# Smart_water_dispenser.net
KiCad netlist of a schematic drawn in Altium Designer
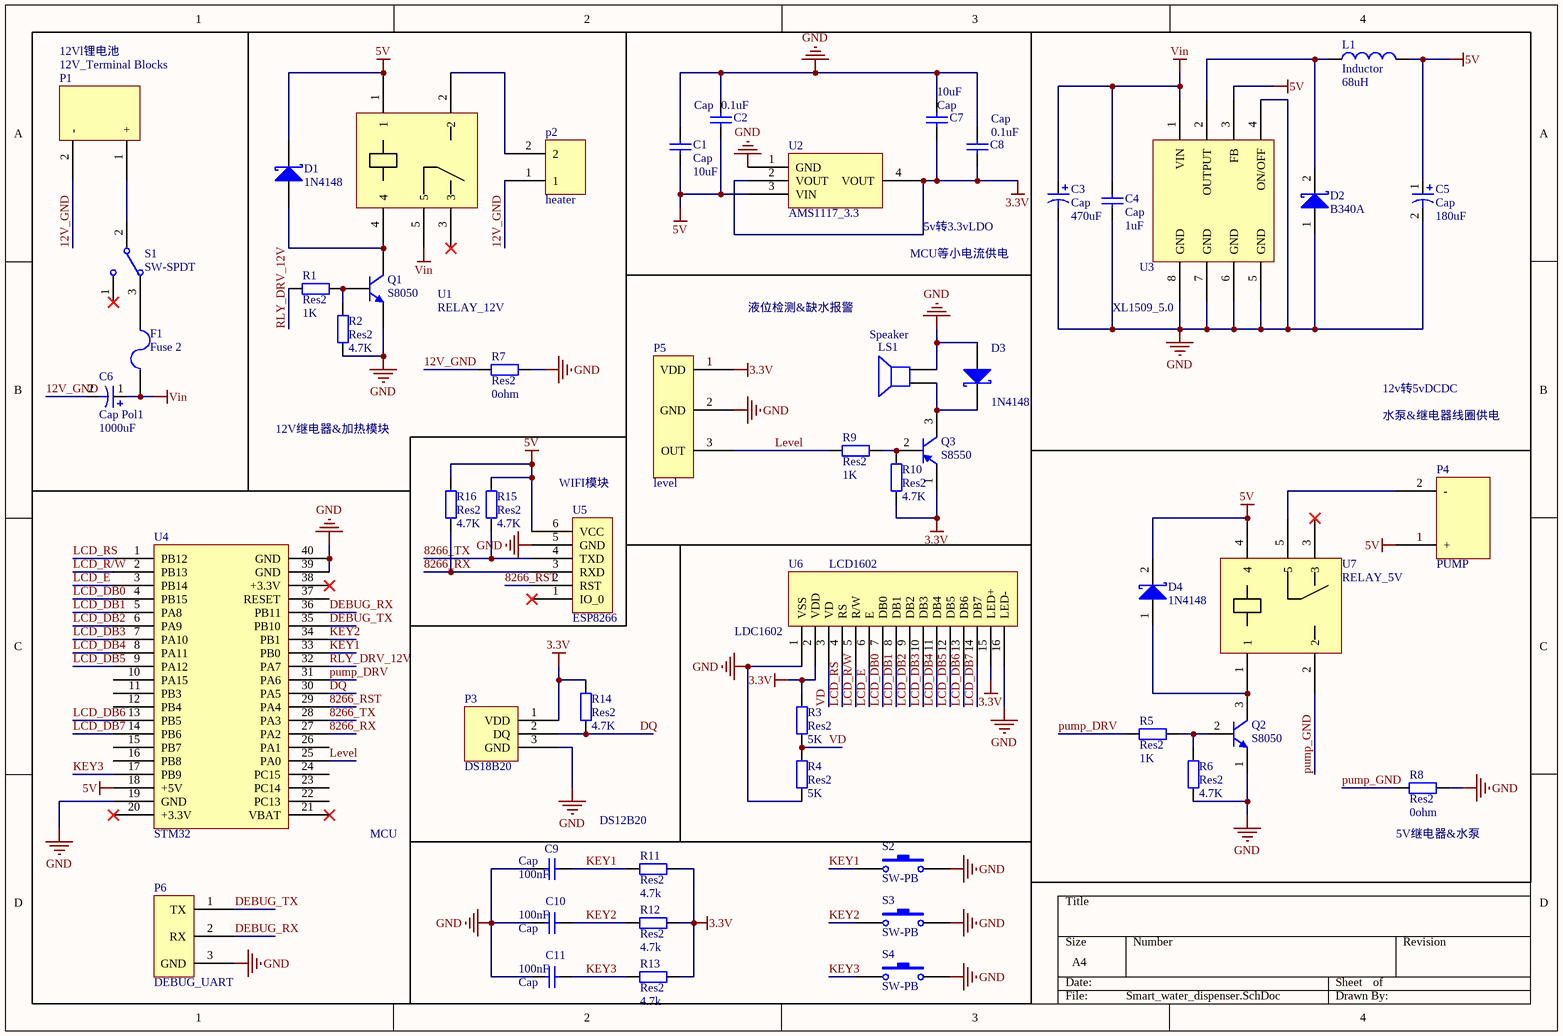
[diagram p0: Smart_water_dispenser.SchDoc]

(export (version "E")
  (design (tool "Eeschema 10.0.6"))
  (components
    (comp (ref "C1")
      (value "Cap")
      (footprint "0805")
      (description "Capacitor")
      (fields (field (name "ALTIUM_VALUE") "10uF") (field (name "PUBLISHER") "Altium Limited"))
      (libsource (lib "Miscellaneous Devices") (part "Cap"))
    )
    (comp (ref "C2")
      (value "Cap")
      (footprint "0805")
      (description "Capacitor")
      (fields (field (name "ALTIUM_VALUE") "0.1uF") (field (name "PUBLISHER") "Altium Limited"))
      (libsource (lib "Miscellaneous Devices") (part "Cap"))
    )
    (comp (ref "C3")
      (value "Cap")
      (footprint "CAP_TH_BD10")
      (description "Polarized Capacitor (Radial)")
      (fields (field (name "ALTIUM_VALUE") "470uF") (field (name "PUBLISHER") "Altium Limited"))
      (libsource (lib "") (part "Cap Pol1_1"))
    )
    (comp (ref "C4")
      (value "Cap")
      (footprint "0805")
      (description "Capacitor")
      (fields (field (name "ALTIUM_VALUE") "1uF") (field (name "PUBLISHER") "Altium Limited"))
      (libsource (lib "Miscellaneous Devices") (part "Cap"))
    )
    (comp (ref "C5")
      (value "Cap")
      (footprint "CAP_TH_BD10")
      (description "Polarized Capacitor (Radial)")
      (fields (field (name "ALTIUM_VALUE") "180uF") (field (name "PUBLISHER") "Altium Limited"))
      (libsource (lib "Miscellaneous Devices") (part "Cap Pol1"))
    )
    (comp (ref "C6")
      (value "Cap Pol1")
      (footprint "cap_1000uF")
      (description "Polarized Capacitor (Radial)")
      (fields (field (name "ALTIUM_VALUE") "1000uF") (field (name "PUBLISHER") "Altium Limited"))
      (libsource (lib "Miscellaneous Devices") (part "Cap Pol1"))
    )
    (comp (ref "C7")
      (value "Cap")
      (footprint "0805")
      (description "Capacitor")
      (fields (field (name "ALTIUM_VALUE") "10uF") (field (name "PUBLISHER") "Altium Limited"))
      (libsource (lib "Miscellaneous Devices") (part "Cap"))
    )
    (comp (ref "C8")
      (value "Cap")
      (footprint "0805")
      (description "Capacitor")
      (fields (field (name "ALTIUM_VALUE") "0.1uF") (field (name "PUBLISHER") "Altium Limited"))
      (libsource (lib "Miscellaneous Devices") (part "Cap"))
    )
    (comp (ref "C9")
      (value "Cap")
      (footprint "0805")
      (description "Capacitor")
      (fields (field (name "ALTIUM_VALUE") "100nF") (field (name "PUBLISHER") "Altium Limited"))
      (libsource (lib "Miscellaneous Devices") (part "Cap"))
    )
    (comp (ref "C10")
      (value "Cap")
      (footprint "0805")
      (description "Capacitor")
      (fields (field (name "ALTIUM_VALUE") "100nF") (field (name "PUBLISHER") "Altium Limited"))
      (libsource (lib "Miscellaneous Devices") (part "Cap"))
    )
    (comp (ref "C11")
      (value "Cap")
      (footprint "0805")
      (description "Capacitor")
      (fields (field (name "ALTIUM_VALUE") "100nF") (field (name "PUBLISHER") "Altium Limited"))
      (libsource (lib "Miscellaneous Devices") (part "Cap"))
    )
    (comp (ref "D1")
      (value "1N4148")
      (footprint "1N4148")
      (description "Schottky Diode")
      (fields (field (name "PUBLISHER") "Altium Limited"))
      (libsource (lib "") (part "D Schottky_1"))
    )
    (comp (ref "D2")
      (value "B340A")
      (footprint "B340A")
      (description "Schottky Diode")
      (fields (field (name "PUBLISHER") "Altium Limited"))
      (libsource (lib "Miscellaneous Devices") (part "D Schottky"))
    )
    (comp (ref "D3")
      (value "1N4148")
      (footprint "1N4148")
      (description "Schottky Diode")
      (fields (field (name "PUBLISHER") "Altium Limited"))
      (libsource (lib "") (part "D Schottky_1"))
    )
    (comp (ref "D4")
      (value "1N4148")
      (footprint "1N4148")
      (description "Schottky Diode")
      (fields (field (name "PUBLISHER") "Altium Limited"))
      (libsource (lib "Miscellaneous Devices") (part "D Schottky"))
    )
    (comp (ref "F1")
      (value "Fuse 2")
      (footprint "F1812")
      (description "Fuse")
      (fields (field (name "PUBLISHER") "Altium Limited"))
      (libsource (lib "Miscellaneous Devices") (part "Fuse 2"))
    )
    (comp (ref "L1")
      (value "Inductor")
      (footprint "IND_CD54")
      (fields (field (name "ALTIUM_VALUE") "68uH") (field (name "PUBLISHER") "Altium Limited"))
      (libsource (lib "Miscellaneous Devices") (part "Inductor"))
    )
    (comp (ref "LS1")
      (value "Speaker")
      (footprint "buzzer")
      (description "Loudspeaker")
      (fields (field (name "PUBLISHER") "Altium Limited"))
      (libsource (lib "Miscellaneous Devices") (part "Speaker"))
    )
    (comp (ref "P1")
      (value "12V_Terminal Blocks")
      (footprint "2PIN")
      (libsource (lib "智能饮水机") (part "12V_Terminal Blocks"))
    )
    (comp (ref "p2") (value "heater") (footprint "2PIN") (libsource (lib "智能饮水机") (part "heater")))
    (comp (ref "P3") (value "DS18B20") (footprint "DS18B20") (libsource (lib "智能饮水机") (part "DS18B20")))
    (comp (ref "P4") (value "PUMP") (footprint "2PIN") (libsource (lib "智能饮水机") (part "PUMP")))
    (comp (ref "P5") (value "level") (footprint "DS18B20") (libsource (lib "智能饮水机") (part "level")))
    (comp (ref "P6")
      (value "DEBUG_UART")
      (footprint "DEBUG_UART")
      (libsource (lib "智能饮水机") (part "DEBUG_UART"))
    )
    (comp (ref "Q1")
      (value "S8050")
      (footprint "S8050")
      (description "NPN General Purpose Amplifier")
      (fields (field (name "PUBLISHER") "Altium Limited"))
      (libsource (lib "Miscellaneous Devices") (part "2N3904"))
    )
    (comp (ref "Q2")
      (value "S8050")
      (footprint "S8050")
      (description "NPN General Purpose Amplifier")
      (fields (field (name "PUBLISHER") "Altium Limited"))
      (libsource (lib "") (part "2N3904_1"))
    )
    (comp (ref "Q3")
      (value "S8550")
      (footprint "S8050")
      (description "PNP General Purpose Amplifier")
      (fields (field (name "PUBLISHER") "Altium Limited"))
      (libsource (lib "Miscellaneous Devices") (part "2N3906"))
    )
    (comp (ref "R1")
      (value "Res2")
      (footprint "0805")
      (description "Resistor")
      (fields (field (name "ALTIUM_VALUE") "1K") (field (name "PUBLISHER") "Altium Limited"))
      (libsource (lib "Miscellaneous Devices") (part "Res2"))
    )
    (comp (ref "R2")
      (value "Res2")
      (footprint "0805")
      (description "Resistor")
      (fields (field (name "ALTIUM_VALUE") "4.7K") (field (name "PUBLISHER") "Altium Limited"))
      (libsource (lib "") (part "Res2_2"))
    )
    (comp (ref "R3")
      (value "Res2")
      (footprint "0805")
      (description "Resistor")
      (fields (field (name "ALTIUM_VALUE") "5K") (field (name "PUBLISHER") "Altium Limited"))
      (libsource (lib "") (part "Res2_2"))
    )
    (comp (ref "R4")
      (value "Res2")
      (footprint "0805")
      (description "Resistor")
      (fields (field (name "ALTIUM_VALUE") "5K") (field (name "PUBLISHER") "Altium Limited"))
      (libsource (lib "") (part "Res2_2"))
    )
    (comp (ref "R5")
      (value "Res2")
      (footprint "0805")
      (description "Resistor")
      (fields (field (name "ALTIUM_VALUE") "1K") (field (name "PUBLISHER") "Altium Limited"))
      (libsource (lib "Miscellaneous Devices") (part "Res2"))
    )
    (comp (ref "R6")
      (value "Res2")
      (footprint "0805")
      (description "Resistor")
      (fields (field (name "ALTIUM_VALUE") "4.7K") (field (name "PUBLISHER") "Altium Limited"))
      (libsource (lib "") (part "Res2_2"))
    )
    (comp (ref "R7")
      (value "Res2")
      (footprint "0805")
      (description "Resistor")
      (fields (field (name "ALTIUM_VALUE") "0ohm") (field (name "PUBLISHER") "Altium Limited"))
      (libsource (lib "Miscellaneous Devices") (part "Res2"))
    )
    (comp (ref "R8")
      (value "Res2")
      (footprint "0805")
      (description "Resistor")
      (fields (field (name "ALTIUM_VALUE") "0ohm") (field (name "PUBLISHER") "Altium Limited"))
      (libsource (lib "Miscellaneous Devices") (part "Res2"))
    )
    (comp (ref "R9")
      (value "Res2")
      (footprint "0805")
      (description "Resistor")
      (fields (field (name "ALTIUM_VALUE") "1K") (field (name "PUBLISHER") "Altium Limited"))
      (libsource (lib "Miscellaneous Devices") (part "Res2"))
    )
    (comp (ref "R10")
      (value "Res2")
      (footprint "0805")
      (description "Resistor")
      (fields (field (name "ALTIUM_VALUE") "4.7K") (field (name "PUBLISHER") "Altium Limited"))
      (libsource (lib "") (part "Res2_2"))
    )
    (comp (ref "R11")
      (value "Res2")
      (footprint "0805")
      (description "Resistor")
      (fields (field (name "ALTIUM_VALUE") "4.7k") (field (name "PUBLISHER") "Altium Limited"))
      (libsource (lib "") (part "Res2_1"))
    )
    (comp (ref "R12")
      (value "Res2")
      (footprint "0805")
      (description "Resistor")
      (fields (field (name "ALTIUM_VALUE") "4.7k") (field (name "PUBLISHER") "Altium Limited"))
      (libsource (lib "") (part "Res2_1"))
    )
    (comp (ref "R13")
      (value "Res2")
      (footprint "0805")
      (description "Resistor")
      (fields (field (name "ALTIUM_VALUE") "4.7k") (field (name "PUBLISHER") "Altium Limited"))
      (libsource (lib "") (part "Res2_1"))
    )
    (comp (ref "R14")
      (value "Res2")
      (footprint "0805")
      (description "Resistor")
      (fields (field (name "ALTIUM_VALUE") "4.7K") (field (name "PUBLISHER") "Altium Limited"))
      (libsource (lib "") (part "Res2_2"))
    )
    (comp (ref "R15")
      (value "Res2")
      (footprint "0805")
      (description "Resistor")
      (fields (field (name "ALTIUM_VALUE") "4.7K") (field (name "PUBLISHER") "Altium Limited"))
      (libsource (lib "") (part "Res2_2"))
    )
    (comp (ref "R16")
      (value "Res2")
      (footprint "0805")
      (description "Resistor")
      (fields (field (name "ALTIUM_VALUE") "4.7K") (field (name "PUBLISHER") "Altium Limited"))
      (libsource (lib "") (part "Res2_2"))
    )
    (comp (ref "S1")
      (value "SW-SPDT")
      (footprint "SW")
      (description "SPDT Subminiature Toggle Switch, Right Angle Mounting, Vertical Actuation")
      (fields (field (name "PUBLISHER") "Altium Limited"))
      (libsource (lib "Miscellaneous Devices") (part "SW-SPDT"))
    )
    (comp (ref "S2")
      (value "SW-PB")
      (footprint "SW2")
      (description "Switch")
      (fields (field (name "PUBLISHER") "Altium Limited"))
      (libsource (lib "Miscellaneous Devices") (part "SW-PB"))
    )
    (comp (ref "S3")
      (value "SW-PB")
      (footprint "SW2")
      (description "Switch")
      (fields (field (name "PUBLISHER") "Altium Limited"))
      (libsource (lib "Miscellaneous Devices") (part "SW-PB"))
    )
    (comp (ref "S4")
      (value "SW-PB")
      (footprint "SW2")
      (description "Switch")
      (fields (field (name "PUBLISHER") "Altium Limited"))
      (libsource (lib "Miscellaneous Devices") (part "SW-PB"))
    )
    (comp (ref "U1") (value "RELAY_12V") (footprint "RELAY") (libsource (lib "智能饮水机") (part "RELAY_12V")))
    (comp (ref "U2")
      (value "AMS1117_3.3")
      (footprint "AMS1117")
      (libsource (lib "智能饮水机") (part "AMS1117_3.3"))
    )
    (comp (ref "U3")
      (value "XL1509_5.0")
      (footprint "XL1509_5.0")
      (libsource (lib "智能饮水机") (part "XL1509_5.0"))
    )
    (comp (ref "U4") (value "STM32") (footprint "STM32") (libsource (lib "智能饮水机") (part "STM32")))
    (comp (ref "U5") (value "ESP8266") (footprint "ESP8266") (libsource (lib "智能饮水机") (part "ESP8266")))
    (comp (ref "U6") (value "LCD1602") (footprint "LCD1602") (libsource (lib "智能饮水机") (part "LCD1602")))
    (comp (ref "U7") (value "RELAY_5V") (footprint "RELAY") (libsource (lib "智能饮水机") (part "RELAY_5V")))
  )
  (nets
    (net (code "1") (name "/12V_GND") (class "Default")
      (node (ref "C6") (pin "2") (pinfunction "2_2") (pintype "passive"))
      (node (ref "P1") (pin "2") (pinfunction "-_2") (pintype "passive"))
      (node (ref "R7") (pin "1") (pinfunction "1_1") (pintype "passive"))
      (node (ref "p2") (pin "1") (pinfunction "1_1") (pintype "passive"))
    )
    (net (code "2") (name "/8266_RST") (class "Default")
      (node (ref "U4") (pin "29") (pinfunction "PA4_29") (pintype "passive"))
      (node (ref "U5") (pin "2") (pinfunction "RST_2") (pintype "passive"))
    )
    (net (code "3") (name "/8266_RX") (class "Default")
      (node (ref "R16") (pin "1") (pinfunction "1_1") (pintype "passive"))
      (node (ref "U4") (pin "27") (pinfunction "PA2_27") (pintype "passive"))
      (node (ref "U5") (pin "3") (pinfunction "RXD_3") (pintype "passive"))
    )
    (net (code "4") (name "/8266_TX") (class "Default")
      (node (ref "R15") (pin "1") (pinfunction "1_1") (pintype "passive"))
      (node (ref "U4") (pin "28") (pinfunction "PA3_28") (pintype "passive"))
      (node (ref "U5") (pin "4") (pinfunction "TXD_4") (pintype "passive"))
    )
    (net (code "5") (name "/DEBUG_RX") (class "Default")
      (node (ref "P6") (pin "2") (pinfunction "RX_2") (pintype "passive"))
      (node (ref "U4") (pin "36") (pinfunction "PB11_36") (pintype "passive"))
    )
    (net (code "6") (name "/DEBUG_TX") (class "Default")
      (node (ref "P6") (pin "1") (pinfunction "TX_1") (pintype "passive"))
      (node (ref "U4") (pin "35") (pinfunction "PB10_35") (pintype "passive"))
    )
    (net (code "7") (name "/DQ") (class "Default")
      (node (ref "P3") (pin "2") (pinfunction "DQ_2") (pintype "passive"))
      (node (ref "R14") (pin "1") (pinfunction "1_1") (pintype "passive"))
      (node (ref "U4") (pin "30") (pinfunction "PA5_30") (pintype "passive"))
    )
    (net (code "8") (name "/KEY1") (class "Default")
      (node (ref "C9") (pin "2") (pinfunction "2_2") (pintype "passive"))
      (node (ref "R11") (pin "2") (pinfunction "2_2") (pintype "passive"))
      (node (ref "S2") (pin "1") (pinfunction "1_1") (pintype "passive"))
      (node (ref "U4") (pin "33") (pinfunction "PB0_33") (pintype "passive"))
    )
    (net (code "9") (name "/KEY2") (class "Default")
      (node (ref "C10") (pin "2") (pinfunction "2_2") (pintype "passive"))
      (node (ref "R12") (pin "2") (pinfunction "2_2") (pintype "passive"))
      (node (ref "S3") (pin "1") (pinfunction "1_1") (pintype "passive"))
      (node (ref "U4") (pin "34") (pinfunction "PB1_34") (pintype "passive"))
    )
    (net (code "10") (name "/KEY3") (class "Default")
      (node (ref "C11") (pin "2") (pinfunction "2_2") (pintype "passive"))
      (node (ref "R13") (pin "2") (pinfunction "2_2") (pintype "passive"))
      (node (ref "S4") (pin "1") (pinfunction "1_1") (pintype "passive"))
      (node (ref "U4") (pin "17") (pinfunction "PB9_17") (pintype "passive"))
    )
    (net (code "11") (name "/LCD_DB0") (class "Default")
      (node (ref "U4") (pin "4") (pinfunction "PB15_4") (pintype "passive"))
      (node (ref "U6") (pin "7") (pinfunction "DB0_7") (pintype "passive"))
    )
    (net (code "12") (name "/LCD_DB1") (class "Default")
      (node (ref "U4") (pin "5") (pinfunction "PA8_5") (pintype "passive"))
      (node (ref "U6") (pin "8") (pinfunction "DB1_8") (pintype "passive"))
    )
    (net (code "13") (name "/LCD_DB2") (class "Default")
      (node (ref "U4") (pin "6") (pinfunction "PA9_6") (pintype "passive"))
      (node (ref "U6") (pin "9") (pinfunction "DB2_9") (pintype "passive"))
    )
    (net (code "14") (name "/LCD_DB3") (class "Default")
      (node (ref "U4") (pin "7") (pinfunction "PA10_7") (pintype "passive"))
      (node (ref "U6") (pin "10") (pinfunction "DB3_10") (pintype "passive"))
    )
    (net (code "15") (name "/LCD_DB4") (class "Default")
      (node (ref "U4") (pin "8") (pinfunction "PA11_8") (pintype "passive"))
      (node (ref "U6") (pin "11") (pinfunction "DB4_11") (pintype "passive"))
    )
    (net (code "16") (name "/LCD_DB5") (class "Default")
      (node (ref "U4") (pin "9") (pinfunction "PA12_9") (pintype "passive"))
      (node (ref "U6") (pin "12") (pinfunction "DB5_12") (pintype "passive"))
    )
    (net (code "17") (name "/LCD_DB6") (class "Default")
      (node (ref "U4") (pin "13") (pinfunction "PB5_13") (pintype "passive"))
      (node (ref "U6") (pin "13") (pinfunction "DB6_13") (pintype "passive"))
    )
    (net (code "18") (name "/LCD_DB7") (class "Default")
      (node (ref "U4") (pin "14") (pinfunction "PB6_14") (pintype "passive"))
      (node (ref "U6") (pin "14") (pinfunction "DB7_14") (pintype "passive"))
    )
    (net (code "19") (name "/LCD_E") (class "Default")
      (node (ref "U4") (pin "3") (pinfunction "PB14_3") (pintype "passive"))
      (node (ref "U6") (pin "6") (pinfunction "E_6") (pintype "passive"))
    )
    (net (code "20") (name "/LCD_RS") (class "Default")
      (node (ref "U4") (pin "1") (pinfunction "PB12_1") (pintype "passive"))
      (node (ref "U6") (pin "4") (pinfunction "RS_4") (pintype "passive"))
    )
    (net (code "21") (name "/LCD_R{slash}W") (class "Default")
      (node (ref "U4") (pin "2") (pinfunction "PB13_2") (pintype "passive"))
      (node (ref "U6") (pin "5") (pinfunction "R/W_5") (pintype "passive"))
    )
    (net (code "22") (name "/Level") (class "Default")
      (node (ref "P5") (pin "3") (pinfunction "OUT_3") (pintype "passive"))
      (node (ref "R9") (pin "1") (pinfunction "1_1") (pintype "passive"))
      (node (ref "U4") (pin "25") (pinfunction "PA0_25") (pintype "passive"))
    )
    (net (code "23") (name "/RLY_DRV_12V") (class "Default")
      (node (ref "R1") (pin "1") (pinfunction "1_1") (pintype "passive"))
      (node (ref "U4") (pin "32") (pinfunction "PA7_32") (pintype "passive"))
    )
    (net (code "24") (name "/VD") (class "Default")
      (node (ref "R3") (pin "1") (pinfunction "1_1") (pintype "passive"))
      (node (ref "R4") (pin "2") (pinfunction "2_2") (pintype "passive"))
      (node (ref "U6") (pin "3") (pinfunction "VD_3") (pintype "passive"))
    )
    (net (code "25") (name "/pump_DRV") (class "Default")
      (node (ref "R5") (pin "1") (pinfunction "1_1") (pintype "passive"))
      (node (ref "U4") (pin "31") (pinfunction "PA6_31") (pintype "passive"))
    )
    (net (code "26") (name "/pump_GND") (class "Default")
      (node (ref "R8") (pin "1") (pinfunction "1_1") (pintype "passive"))
      (node (ref "U7") (pin "2") (pinfunction "2_2") (pintype "passive"))
    )
    (net (code "27") (name "3.3V") (class "Default")
      (node (ref "C7") (pin "1") (pinfunction "1_1") (pintype "passive"))
      (node (ref "C8") (pin "1") (pinfunction "1_1") (pintype "passive"))
      (node (ref "P3") (pin "1") (pinfunction "VDD_1") (pintype "passive"))
      (node (ref "P5") (pin "1") (pinfunction "VDD_1") (pintype "passive"))
      (node (ref "Q3") (pin "1") (pinfunction "E_1") (pintype "passive"))
      (node (ref "R10") (pin "1") (pinfunction "1_1") (pintype "passive"))
      (node (ref "R11") (pin "1") (pinfunction "1_1") (pintype "passive"))
      (node (ref "R12") (pin "1") (pinfunction "1_1") (pintype "passive"))
      (node (ref "R13") (pin "1") (pinfunction "1_1") (pintype "passive"))
      (node (ref "R14") (pin "2") (pinfunction "2_2") (pintype "passive"))
      (node (ref "R3") (pin "2") (pinfunction "2_2") (pintype "passive"))
      (node (ref "U2") (pin "2") (pinfunction "VOUT_2") (pintype "passive"))
      (node (ref "U2") (pin "4") (pinfunction "VOUT_4") (pintype "passive"))
      (node (ref "U6") (pin "15") (pinfunction "LED+_15") (pintype "passive"))
      (node (ref "U6") (pin "2") (pinfunction "VDD_2") (pintype "passive"))
    )
    (net (code "28") (name "5V") (class "Default")
      (node (ref "C1") (pin "2") (pinfunction "2_2") (pintype "passive"))
      (node (ref "C2") (pin "1") (pinfunction "1_1") (pintype "passive"))
      (node (ref "C5") (pin "1") (pinfunction "1_1") (pintype "passive"))
      (node (ref "D1") (pin "2") (pinfunction "K_2") (pintype "passive"))
      (node (ref "D4") (pin "2") (pinfunction "K_2") (pintype "passive"))
      (node (ref "L1") (pin "2") (pinfunction "2_2") (pintype "passive"))
      (node (ref "P4") (pin "1") (pinfunction "+_1") (pintype "passive"))
      (node (ref "R15") (pin "2") (pinfunction "2_2") (pintype "passive"))
      (node (ref "R16") (pin "2") (pinfunction "2_2") (pintype "passive"))
      (node (ref "U1") (pin "1") (pinfunction "1_1") (pintype "passive"))
      (node (ref "U2") (pin "3") (pinfunction "VIN_3") (pintype "passive"))
      (node (ref "U3") (pin "3") (pinfunction "FB_3") (pintype "passive"))
      (node (ref "U4") (pin "18") (pinfunction "+5V_18") (pintype "passive"))
      (node (ref "U5") (pin "6") (pinfunction "VCC_6") (pintype "passive"))
      (node (ref "U7") (pin "4") (pinfunction "4_4") (pintype "passive"))
    )
    (net (code "29") (name "GND") (class "Default")
      (node (ref "C1") (pin "1") (pinfunction "1_1") (pintype "passive"))
      (node (ref "C10") (pin "1") (pinfunction "1_1") (pintype "passive"))
      (node (ref "C11") (pin "1") (pinfunction "1_1") (pintype "passive"))
      (node (ref "C2") (pin "2") (pinfunction "2_2") (pintype "passive"))
      (node (ref "C3") (pin "2") (pinfunction "2_2") (pintype "passive"))
      (node (ref "C4") (pin "1") (pinfunction "1_1") (pintype "passive"))
      (node (ref "C5") (pin "2") (pinfunction "2_2") (pintype "passive"))
      (node (ref "C7") (pin "2") (pinfunction "2_2") (pintype "passive"))
      (node (ref "C8") (pin "2") (pinfunction "2_2") (pintype "passive"))
      (node (ref "C9") (pin "1") (pinfunction "1_1") (pintype "passive"))
      (node (ref "D2") (pin "1") (pinfunction "A_1") (pintype "passive"))
      (node (ref "D3") (pin "1") (pinfunction "A_1") (pintype "passive"))
      (node (ref "LS1") (pin "2") (pinfunction "2_2") (pintype "passive"))
      (node (ref "P3") (pin "3") (pinfunction "GND_3") (pintype "passive"))
      (node (ref "P5") (pin "2") (pinfunction "GND_2") (pintype "passive"))
      (node (ref "P6") (pin "3") (pinfunction "GND_3") (pintype "passive"))
      (node (ref "Q1") (pin "1") (pinfunction "E_1") (pintype "passive"))
      (node (ref "Q2") (pin "1") (pinfunction "E_1") (pintype "passive"))
      (node (ref "R2") (pin "1") (pinfunction "1_1") (pintype "passive"))
      (node (ref "R4") (pin "1") (pinfunction "1_1") (pintype "passive"))
      (node (ref "R6") (pin "1") (pinfunction "1_1") (pintype "passive"))
      (node (ref "R7") (pin "2") (pinfunction "2_2") (pintype "passive"))
      (node (ref "R8") (pin "2") (pinfunction "2_2") (pintype "passive"))
      (node (ref "S2") (pin "2") (pinfunction "2_2") (pintype "passive"))
      (node (ref "S3") (pin "2") (pinfunction "2_2") (pintype "passive"))
      (node (ref "S4") (pin "2") (pinfunction "2_2") (pintype "passive"))
      (node (ref "U2") (pin "1") (pinfunction "GND_1") (pintype "passive"))
      (node (ref "U3") (pin "4") (pinfunction "ON/OFF_4") (pintype "passive"))
      (node (ref "U3") (pin "5") (pinfunction "GND_5") (pintype "passive"))
      (node (ref "U3") (pin "6") (pinfunction "GND_6") (pintype "passive"))
      (node (ref "U3") (pin "7") (pinfunction "GND_7") (pintype "passive"))
      (node (ref "U3") (pin "8") (pinfunction "GND_8") (pintype "passive"))
      (node (ref "U4") (pin "19") (pinfunction "GND_19") (pintype "passive"))
      (node (ref "U4") (pin "39") (pinfunction "GND_39") (pintype "passive"))
      (node (ref "U4") (pin "40") (pinfunction "GND_40") (pintype "passive"))
      (node (ref "U5") (pin "5") (pinfunction "GND_5") (pintype "passive"))
      (node (ref "U6") (pin "1") (pinfunction "VSS_1") (pintype "passive"))
      (node (ref "U6") (pin "16") (pinfunction "LED-_16") (pintype "passive"))
    )
    (net (code "30") (name "Net-(D1-A)") (class "Default")
      (node (ref "D1") (pin "1") (pinfunction "A_1") (pintype "passive"))
      (node (ref "Q1") (pin "3") (pinfunction "C_3") (pintype "passive"))
      (node (ref "U1") (pin "4") (pinfunction "4_4") (pintype "passive"))
    )
    (net (code "31") (name "Net-(D2-K)") (class "Default")
      (node (ref "D2") (pin "2") (pinfunction "K_2") (pintype "passive"))
      (node (ref "L1") (pin "1") (pinfunction "1_1") (pintype "passive"))
      (node (ref "U3") (pin "2") (pinfunction "OUTPUT_2") (pintype "passive"))
    )
    (net (code "32") (name "Net-(D3-K)") (class "Default")
      (node (ref "D3") (pin "2") (pinfunction "K_2") (pintype "passive"))
      (node (ref "LS1") (pin "1") (pinfunction "1_1") (pintype "passive"))
      (node (ref "Q3") (pin "3") (pinfunction "C_3") (pintype "passive"))
    )
    (net (code "33") (name "Net-(D4-A)") (class "Default")
      (node (ref "D4") (pin "1") (pinfunction "A_1") (pintype "passive"))
      (node (ref "Q2") (pin "3") (pinfunction "C_3") (pintype "passive"))
      (node (ref "U7") (pin "1") (pinfunction "1_1") (pintype "passive"))
    )
    (net (code "34") (name "Net-(F1-Pad2)") (class "Default")
      (node (ref "F1") (pin "2") (pinfunction "2_2") (pintype "passive"))
      (node (ref "S1") (pin "3") (pinfunction "3_3") (pintype "passive"))
    )
    (net (code "35") (name "Net-(P1-+)") (class "Default")
      (node (ref "P1") (pin "1") (pinfunction "+_1") (pintype "passive"))
      (node (ref "S1") (pin "2") (pinfunction "2_2") (pintype "passive"))
    )
    (net (code "36") (name "Net-(P4--)") (class "Default")
      (node (ref "P4") (pin "2") (pinfunction "-_2") (pintype "passive"))
      (node (ref "U7") (pin "5") (pinfunction "5_5") (pintype "passive"))
    )
    (net (code "37") (name "Net-(Q1-B)") (class "Default")
      (node (ref "Q1") (pin "2") (pinfunction "B_2") (pintype "passive"))
      (node (ref "R1") (pin "2") (pinfunction "2_2") (pintype "passive"))
      (node (ref "R2") (pin "2") (pinfunction "2_2") (pintype "passive"))
    )
    (net (code "38") (name "Net-(Q2-B)") (class "Default")
      (node (ref "Q2") (pin "2") (pinfunction "B_2") (pintype "passive"))
      (node (ref "R5") (pin "2") (pinfunction "2_2") (pintype "passive"))
      (node (ref "R6") (pin "2") (pinfunction "2_2") (pintype "passive"))
    )
    (net (code "39") (name "Net-(Q3-B)") (class "Default")
      (node (ref "Q3") (pin "2") (pinfunction "B_2") (pintype "passive"))
      (node (ref "R10") (pin "2") (pinfunction "2_2") (pintype "passive"))
      (node (ref "R9") (pin "2") (pinfunction "2_2") (pintype "passive"))
    )
    (net (code "40") (name "Net-(U1-Pad2)") (class "Default")
      (node (ref "U1") (pin "2") (pinfunction "2_2") (pintype "passive"))
      (node (ref "p2") (pin "2") (pinfunction "2_2") (pintype "passive"))
    )
    (net (code "41") (name "Vin") (class "Default")
      (node (ref "C3") (pin "1") (pinfunction "1_1") (pintype "passive"))
      (node (ref "C4") (pin "2") (pinfunction "2_2") (pintype "passive"))
      (node (ref "C6") (pin "1") (pinfunction "1_1") (pintype "passive"))
      (node (ref "F1") (pin "1") (pinfunction "1_1") (pintype "passive"))
      (node (ref "U1") (pin "5") (pinfunction "5_5") (pintype "passive"))
      (node (ref "U3") (pin "1") (pinfunction "VIN_1") (pintype "passive"))
    )
    (net (code "42") (name "unconnected-(S1-Pad1)") (class "Default")
      (node (ref "S1") (pin "1") (pinfunction "1_1") (pintype "passive+no_connect"))
    )
    (net (code "43") (name "unconnected-(U1-Pad3)") (class "Default")
      (node (ref "U1") (pin "3") (pinfunction "3_3") (pintype "passive+no_connect"))
    )
    (net (code "44") (name "unconnected-(U4-+3.3V-Pad20)") (class "Default")
      (node (ref "U4") (pin "20") (pinfunction "+3.3V_20") (pintype "passive+no_connect"))
    )
    (net (code "45") (name "unconnected-(U4-+3.3V-Pad38)") (class "Default")
      (node (ref "U4") (pin "38") (pinfunction "+3.3V_38") (pintype "passive+no_connect"))
    )
    (net (code "46") (name "unconnected-(U4-PA1-Pad26)") (class "Default")
      (node (ref "U4") (pin "26") (pinfunction "PA1_26") (pintype "passive"))
    )
    (net (code "47") (name "unconnected-(U4-PA15-Pad10)") (class "Default")
      (node (ref "U4") (pin "10") (pinfunction "PA15_10") (pintype "passive"))
    )
    (net (code "48") (name "unconnected-(U4-PB3-Pad11)") (class "Default")
      (node (ref "U4") (pin "11") (pinfunction "PB3_11") (pintype "passive"))
    )
    (net (code "49") (name "unconnected-(U4-PB4-Pad12)") (class "Default")
      (node (ref "U4") (pin "12") (pinfunction "PB4_12") (pintype "passive"))
    )
    (net (code "50") (name "unconnected-(U4-PB7-Pad15)") (class "Default")
      (node (ref "U4") (pin "15") (pinfunction "PB7_15") (pintype "passive"))
    )
    (net (code "51") (name "unconnected-(U4-PB8-Pad16)") (class "Default")
      (node (ref "U4") (pin "16") (pinfunction "PB8_16") (pintype "passive"))
    )
    (net (code "52") (name "unconnected-(U4-PC13-Pad22)") (class "Default")
      (node (ref "U4") (pin "22") (pinfunction "PC13_22") (pintype "passive"))
    )
    (net (code "53") (name "unconnected-(U4-PC14-Pad23)") (class "Default")
      (node (ref "U4") (pin "23") (pinfunction "PC14_23") (pintype "passive"))
    )
    (net (code "54") (name "unconnected-(U4-PC15-Pad24)") (class "Default")
      (node (ref "U4") (pin "24") (pinfunction "PC15_24") (pintype "passive"))
    )
    (net (code "55") (name "unconnected-(U4-RESET-Pad37)") (class "Default")
      (node (ref "U4") (pin "37") (pinfunction "RESET_37") (pintype "passive"))
    )
    (net (code "56") (name "unconnected-(U4-VBAT-Pad21)") (class "Default")
      (node (ref "U4") (pin "21") (pinfunction "VBAT_21") (pintype "passive+no_connect"))
    )
    (net (code "57") (name "unconnected-(U5-IO_0-Pad1)") (class "Default")
      (node (ref "U5") (pin "1") (pinfunction "IO_0_1") (pintype "passive+no_connect"))
    )
    (net (code "58") (name "unconnected-(U7-Pad3)") (class "Default")
      (node (ref "U7") (pin "3") (pinfunction "3_3") (pintype "passive+no_connect"))
    )
  )
)
